# controlador.net
KiCad netlist of a schematic drawn in Altium Designer
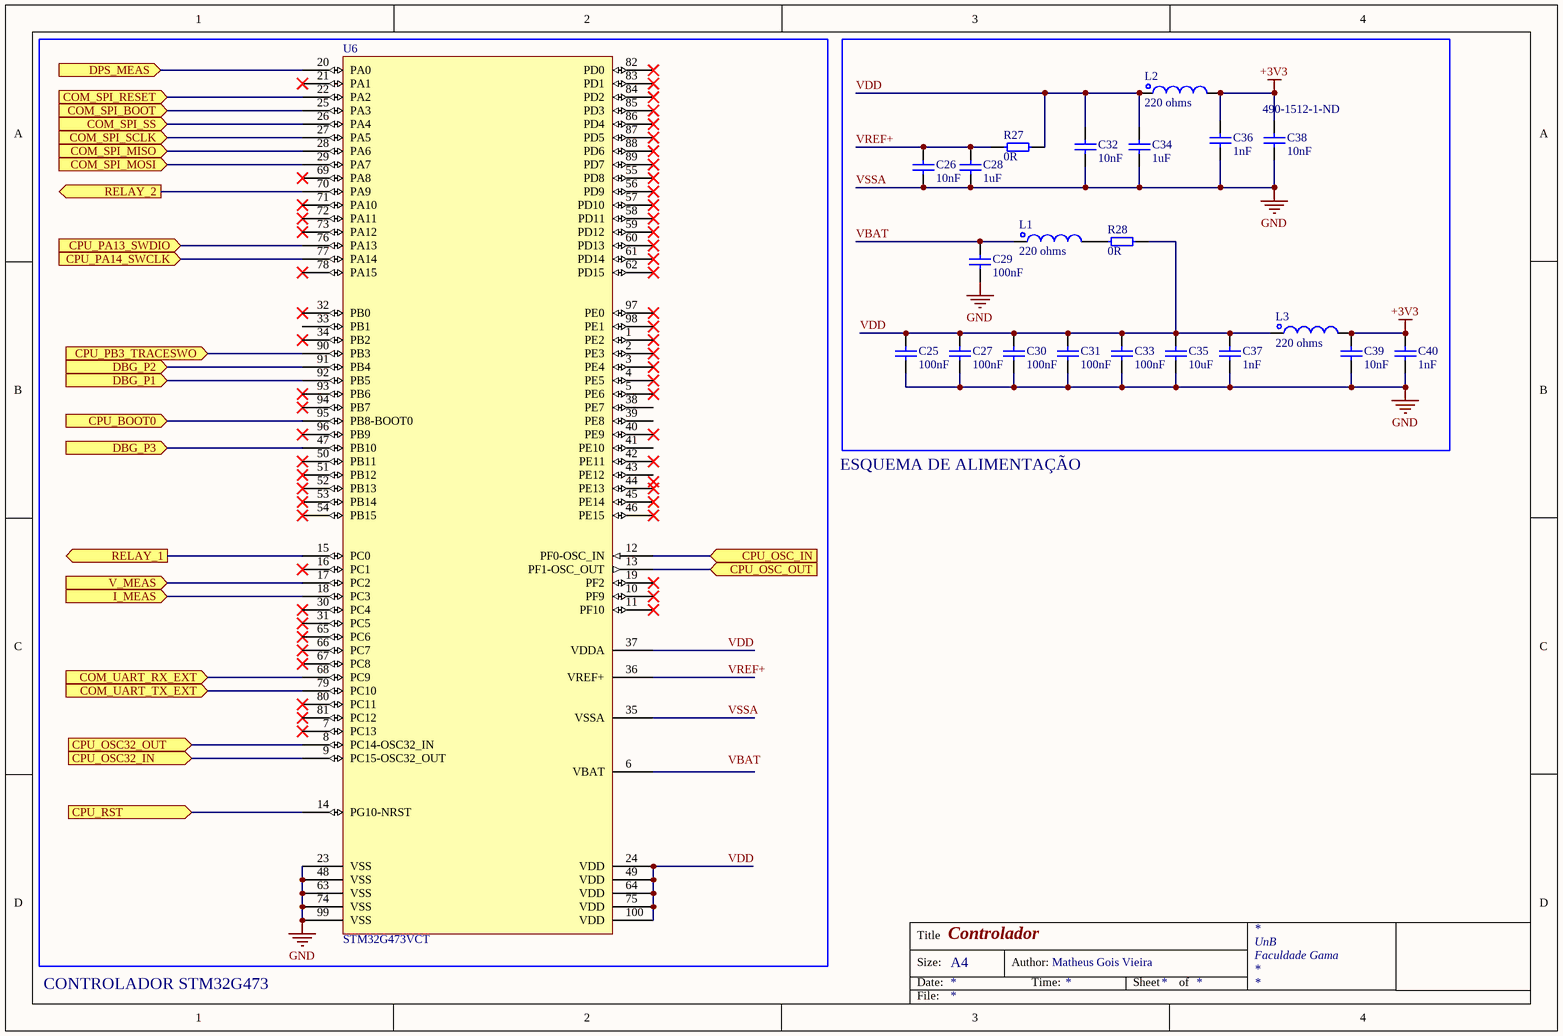
[diagram p0: controlador.SchDoc]

(export (version "E")
  (design (tool "Eeschema 10.0.6"))
  (components
    (comp (ref "C25")
      (value "100nF")
      (footprint "0603")
      (description "Capacitor Ceramic 100nF 20% 50V 0603 (1608 Metric) X7R")
      (fields (field (name "TOLERANCE") "20%") (field (name "MPN") "C0603C104M5RACTU"))
      (libsource (lib "Biblioteca_Clamper") (part "CAP CER SMD-0603 100nF - 50V"))
    )
    (comp (ref "C26")
      (value "10nF")
      (footprint "0603")
      (description "Capacitor Ceramic 10nF 10% 50V 0603 (1608 Metric) X7R")
      (fields (field (name "TOLERANCE") "10%") (field (name "MPN") "06035C103KAT4A"))
      (libsource (lib "Biblioteca_Clamper") (part "CAP CER SMD-0603 10nF - 50V"))
    )
    (comp (ref "C27")
      (value "100nF")
      (footprint "0603")
      (description "Capacitor Ceramic 100nF 20% 50V 0603 (1608 Metric) X7R")
      (fields (field (name "TOLERANCE") "20%") (field (name "MPN") "C0603C104M5RACTU"))
      (libsource (lib "Biblioteca_Clamper") (part "CAP CER SMD-0603 100nF - 50V"))
    )
    (comp (ref "C28")
      (value "1uF")
      (footprint "0603")
      (description "Capacitor Ceramic 1uF 10% 16V 0603 (1608 Metric) X7R")
      (fields (field (name "TOLERANCE") "10%") (field (name "MPN") "0603YC105KAT2A"))
      (libsource (lib "Biblioteca_Clamper") (part "CAP CER SMD-0603 1uF - 16V"))
    )
    (comp (ref "C29")
      (value "100nF")
      (footprint "0603")
      (description "Capacitor Ceramic 100nF 20% 50V 0603 (1608 Metric) X7R")
      (fields (field (name "TOLERANCE") "20%") (field (name "MPN") "C0603C104M5RACTU"))
      (libsource (lib "Biblioteca_Clamper") (part "CAP CER SMD-0603 100nF - 50V"))
    )
    (comp (ref "C30")
      (value "100nF")
      (footprint "0603")
      (description "Capacitor Ceramic 100nF 20% 50V 0603 (1608 Metric) X7R")
      (fields (field (name "TOLERANCE") "20%") (field (name "MPN") "C0603C104M5RACTU"))
      (libsource (lib "Biblioteca_Clamper") (part "CAP CER SMD-0603 100nF - 50V"))
    )
    (comp (ref "C31")
      (value "100nF")
      (footprint "0603")
      (description "Capacitor Ceramic 100nF 20% 50V 0603 (1608 Metric) X7R")
      (fields (field (name "TOLERANCE") "20%") (field (name "MPN") "C0603C104M5RACTU"))
      (libsource (lib "Biblioteca_Clamper") (part "CAP CER SMD-0603 100nF - 50V"))
    )
    (comp (ref "C32")
      (value "10nF")
      (footprint "0603")
      (description "Capacitor Ceramic 10nF 10% 50V 0603 (1608 Metric) X7R")
      (fields (field (name "TOLERANCE") "10%") (field (name "MPN") "06035C103KAT4A"))
      (libsource (lib "Biblioteca_Clamper") (part "CAP CER SMD-0603 10nF - 50V"))
    )
    (comp (ref "C33")
      (value "100nF")
      (footprint "0603")
      (description "Capacitor Ceramic 100nF 20% 50V 0603 (1608 Metric) X7R")
      (fields (field (name "TOLERANCE") "20%") (field (name "MPN") "C0603C104M5RACTU"))
      (libsource (lib "Biblioteca_Clamper") (part "CAP CER SMD-0603 100nF - 50V"))
    )
    (comp (ref "C34")
      (value "1uF")
      (footprint "0603")
      (description "Capacitor Ceramic 1uF 10% 16V 0603 (1608 Metric) X7R")
      (fields (field (name "TOLERANCE") "10%") (field (name "MPN") "0603YC105KAT2A"))
      (libsource (lib "Biblioteca_Clamper") (part "CAP CER SMD-0603 1uF - 16V"))
    )
    (comp (ref "C35")
      (value "10uF")
      (footprint "0603")
      (description "Capacitor Ceramic 10µF 10% 10V 0603 (1608 Metric) X7R")
      (fields (field (name "VOLTAGE") "10V") (field (name "TOLERANCE") "10%"))
      (libsource (lib "Biblioteca_Clamper") (part "CAP CER SMD-0603 10uF - 10V"))
    )
    (comp (ref "C36")
      (value "1nF")
      (footprint "0603")
      (description "Capacitor Ceramic 1nF 5% 50V 0603 (1608 Metric) C0G (NP0)")
      (fields (field (name "TOLERANCE") "5%") (field (name "MPN") "GRM1885C1H102JA01D"))
      (libsource (lib "Biblioteca_Clamper") (part "CAP CER SMD-0603 1nF - 50V"))
    )
    (comp (ref "C37")
      (value "1nF")
      (footprint "0603")
      (description "Capacitor Ceramic 1nF 5% 50V 0603 (1608 Metric) C0G (NP0)")
      (fields (field (name "TOLERANCE") "5%") (field (name "MPN") "GRM1885C1H102JA01D"))
      (libsource (lib "Biblioteca_Clamper") (part "CAP CER SMD-0603 1nF - 50V"))
    )
    (comp (ref "C38")
      (value "10nF")
      (footprint "0603")
      (description "Capacitor Ceramic 10nF 10% 50V 0603 (1608 Metric) X7R")
      (fields
        (field (name "TOLERANCE") "10%")
        (field (name "MPN") "06035C103KAT4A")
        (field (name "SUPPLIER PART NUMBER 1") "490-1512-1-ND")
      )
      (libsource (lib "Biblioteca_Clamper") (part "CAP CER SMD-0603 10nF - 50V"))
    )
    (comp (ref "C39")
      (value "10nF")
      (footprint "0603")
      (description "Capacitor Ceramic 10nF 10% 50V 0603 (1608 Metric) X7R")
      (fields (field (name "TOLERANCE") "10%") (field (name "MPN") "06035C103KAT4A"))
      (libsource (lib "Biblioteca_Clamper") (part "CAP CER SMD-0603 10nF - 50V"))
    )
    (comp (ref "C40")
      (value "1nF")
      (footprint "0603")
      (description "Capacitor Ceramic 1nF 5% 50V 0603 (1608 Metric) C0G (NP0)")
      (fields (field (name "TOLERANCE") "5%") (field (name "MPN") "GRM1885C1H102JA01D"))
      (libsource (lib "Biblioteca_Clamper") (part "CAP CER SMD-0603 1nF - 50V"))
    )
    (comp (ref "L1")
      (value "220 ohms")
      (footprint "0603")
      (description "INDUTOR BEAD - 2.2A - 220 OHMS 100 MHZ")
      (fields (field (name "TOLERANCE") "25%") (field (name "MPN") "BLM18KG221SZ1D"))
      (libsource (lib "Biblioteca_Clamper") (part "INDUTOR BEAD - 2.2A - 50 OHMS 100 MHZ"))
    )
    (comp (ref "L2")
      (value "220 ohms")
      (footprint "0603")
      (description "INDUTOR BEAD - 2.2A - 220 OHMS 100 MHZ")
      (fields (field (name "TOLERANCE") "25%") (field (name "MPN") "BLM18KG221SZ1D"))
      (libsource (lib "Biblioteca_Clamper") (part "INDUTOR BEAD - 2.2A - 50 OHMS 100 MHZ"))
    )
    (comp (ref "L3")
      (value "220 ohms")
      (footprint "0603")
      (description "INDUTOR BEAD - 2.2A - 220 OHMS 100 MHZ")
      (fields (field (name "TOLERANCE") "25%") (field (name "MPN") "BLM18KG221SZ1D"))
      (libsource (lib "Biblioteca_Clamper") (part "INDUTOR BEAD - 2.2A - 50 OHMS 100 MHZ"))
    )
    (comp (ref "R27")
      (value "0R")
      (footprint "0603")
      (description "Resistor Thick Film 0R Jumper 0.1W, 1/10W 0603 (1608 metric) Jumper")
      (fields (field (name "TOLERANCE") "Jumper") (field (name "MPN") "CRCW06030000Z0EA"))
      (libsource (lib "Biblioteca_Clamper") (part "RES SMD-0603 0R 1% 1/10W"))
    )
    (comp (ref "R28")
      (value "0R")
      (footprint "0603")
      (description "Resistor Thick Film 0R Jumper 0.1W, 1/10W 0603 (1608 metric) Jumper")
      (fields (field (name "TOLERANCE") "Jumper") (field (name "MPN") "CRCW06030000Z0EA"))
      (libsource (lib "") (part "RES SMD-0603 0R 1% 1/10W_1"))
    )
    (comp (ref "U6")
      (value "STM32G473VCT")
      (footprint "LQFP100_14MMX14MM")
      (fields (field (name "MANUFACTURER") "ST - Microlectronics"))
      (libsource (lib "Biblioteca_Clamper") (part "STM32G473VCT"))
    )
  )
  (nets
    (net (code "1") (name "+3V3") (class "Default")
      (node (ref "C36") (pin "2") (pinfunction "2_2") (pintype "passive"))
      (node (ref "C38") (pin "2") (pinfunction "2_2") (pintype "passive"))
      (node (ref "C39") (pin "2") (pinfunction "2_2") (pintype "passive"))
      (node (ref "C40") (pin "2") (pinfunction "2_2") (pintype "passive"))
      (node (ref "L2") (pin "2") (pinfunction "2_2") (pintype "passive"))
      (node (ref "L3") (pin "2") (pinfunction "2_2") (pintype "passive"))
    )
    (net (code "2") (name "/COM_SPI_BOOT") (class "Default")
      (node (ref "U6") (pin "25") (pinfunction "PA3_25") (pintype "bidirectional"))
    )
    (net (code "3") (name "/COM_SPI_MISO") (class "Default")
      (node (ref "U6") (pin "28") (pinfunction "PA6_28") (pintype "bidirectional"))
    )
    (net (code "4") (name "/COM_SPI_MOSI") (class "Default")
      (node (ref "U6") (pin "29") (pinfunction "PA7_29") (pintype "bidirectional"))
    )
    (net (code "5") (name "/COM_SPI_RESET") (class "Default")
      (node (ref "U6") (pin "22") (pinfunction "PA2_22") (pintype "bidirectional"))
    )
    (net (code "6") (name "/COM_SPI_SCLK") (class "Default")
      (node (ref "U6") (pin "27") (pinfunction "PA5_27") (pintype "bidirectional"))
    )
    (net (code "7") (name "/COM_SPI_SS") (class "Default")
      (node (ref "U6") (pin "26") (pinfunction "PA4_26") (pintype "bidirectional"))
    )
    (net (code "8") (name "/COM_UART_RX_EXT") (class "Default")
      (node (ref "U6") (pin "68") (pinfunction "PC9_68") (pintype "bidirectional"))
    )
    (net (code "9") (name "/COM_UART_TX_EXT") (class "Default")
      (node (ref "U6") (pin "79") (pinfunction "PC10_79") (pintype "bidirectional"))
    )
    (net (code "10") (name "/CPU_BOOT0") (class "Default")
      (node (ref "U6") (pin "95") (pinfunction "PB8-BOOT0_95") (pintype "bidirectional"))
    )
    (net (code "11") (name "/CPU_OSC32_IN") (class "Default")
      (node (ref "U6") (pin "9") (pinfunction "PC15-OSC32_OUT_9") (pintype "bidirectional"))
    )
    (net (code "12") (name "/CPU_OSC32_OUT") (class "Default")
      (node (ref "U6") (pin "8") (pinfunction "PC14-OSC32_IN_8") (pintype "bidirectional"))
    )
    (net (code "13") (name "/CPU_OSC_IN") (class "Default")
      (node (ref "U6") (pin "12") (pinfunction "PF0-OSC_IN_12") (pintype "input"))
    )
    (net (code "14") (name "/CPU_OSC_OUT") (class "Default")
      (node (ref "U6") (pin "13") (pinfunction "PF1-OSC_OUT_13") (pintype "output"))
    )
    (net (code "15") (name "/CPU_PA13_SWDIO") (class "Default")
      (node (ref "U6") (pin "76") (pinfunction "PA13_76") (pintype "bidirectional"))
    )
    (net (code "16") (name "/CPU_PA14_SWCLK") (class "Default")
      (node (ref "U6") (pin "77") (pinfunction "PA14_77") (pintype "bidirectional"))
    )
    (net (code "17") (name "/CPU_PB3_TRACESWO") (class "Default")
      (node (ref "U6") (pin "90") (pinfunction "PB3_90") (pintype "bidirectional"))
    )
    (net (code "18") (name "/CPU_RST") (class "Default")
      (node (ref "U6") (pin "14") (pinfunction "PG10-NRST_14") (pintype "bidirectional"))
    )
    (net (code "19") (name "/DBG_P1") (class "Default")
      (node (ref "U6") (pin "92") (pinfunction "PB5_92") (pintype "bidirectional"))
    )
    (net (code "20") (name "/DBG_P2") (class "Default")
      (node (ref "U6") (pin "91") (pinfunction "PB4_91") (pintype "bidirectional"))
    )
    (net (code "21") (name "/DBG_P3") (class "Default")
      (node (ref "U6") (pin "47") (pinfunction "PB10_47") (pintype "bidirectional"))
    )
    (net (code "22") (name "/DPS_MEAS") (class "Default")
      (node (ref "U6") (pin "20") (pinfunction "PA0_20") (pintype "bidirectional"))
    )
    (net (code "23") (name "/I_MEAS") (class "Default")
      (node (ref "U6") (pin "18") (pinfunction "PC3_18") (pintype "bidirectional"))
    )
    (net (code "24") (name "/RELAY_1") (class "Default")
      (node (ref "U6") (pin "15") (pinfunction "PC0_15") (pintype "bidirectional"))
    )
    (net (code "25") (name "/RELAY_2") (class "Default")
      (node (ref "U6") (pin "70") (pinfunction "PA9_70") (pintype "bidirectional"))
    )
    (net (code "26") (name "/VBAT") (class "Default")
      (node (ref "C29") (pin "1") (pinfunction "1_1") (pintype "passive"))
      (node (ref "L1") (pin "1") (pinfunction "1_1") (pintype "passive"))
    )
    (net (code "27") (name "/VDD") (class "Default")
      (node (ref "C25") (pin "1") (pinfunction "1_1") (pintype "passive"))
      (node (ref "C27") (pin "1") (pinfunction "1_1") (pintype "passive"))
      (node (ref "C30") (pin "1") (pinfunction "1_1") (pintype "passive"))
      (node (ref "C31") (pin "1") (pinfunction "1_1") (pintype "passive"))
      (node (ref "C32") (pin "2") (pinfunction "2_2") (pintype "passive"))
      (node (ref "C33") (pin "1") (pinfunction "1_1") (pintype "passive"))
      (node (ref "C34") (pin "2") (pinfunction "2_2") (pintype "passive"))
      (node (ref "C35") (pin "2") (pinfunction "2_2") (pintype "passive"))
      (node (ref "C37") (pin "2") (pinfunction "2_2") (pintype "passive"))
      (node (ref "L2") (pin "1") (pinfunction "1_1") (pintype "passive"))
      (node (ref "L3") (pin "1") (pinfunction "1_1") (pintype "passive"))
      (node (ref "R27") (pin "1") (pinfunction "1_1") (pintype "passive"))
      (node (ref "R28") (pin "2") (pinfunction "2_2") (pintype "passive"))
      (node (ref "U6") (pin "100") (pinfunction "VDD_100") (pintype "power_in"))
      (node (ref "U6") (pin "24") (pinfunction "VDD_24") (pintype "power_in"))
      (node (ref "U6") (pin "37") (pinfunction "VDDA_37") (pintype "power_in"))
      (node (ref "U6") (pin "49") (pinfunction "VDD_49") (pintype "power_in"))
      (node (ref "U6") (pin "64") (pinfunction "VDD_64") (pintype "power_in"))
      (node (ref "U6") (pin "75") (pinfunction "VDD_75") (pintype "power_in"))
    )
    (net (code "28") (name "/VREF+") (class "Default")
      (node (ref "C26") (pin "2") (pinfunction "2_2") (pintype "passive"))
      (node (ref "C28") (pin "2") (pinfunction "2_2") (pintype "passive"))
      (node (ref "R27") (pin "2") (pinfunction "2_2") (pintype "passive"))
      (node (ref "U6") (pin "36") (pinfunction "VREF+_36") (pintype "power_in"))
    )
    (net (code "29") (name "/V_MEAS") (class "Default")
      (node (ref "U6") (pin "17") (pinfunction "PC2_17") (pintype "bidirectional"))
    )
    (net (code "30") (name "GND") (class "Default")
      (node (ref "C25") (pin "2") (pinfunction "2_2") (pintype "passive"))
      (node (ref "C26") (pin "1") (pinfunction "1_1") (pintype "passive"))
      (node (ref "C27") (pin "2") (pinfunction "2_2") (pintype "passive"))
      (node (ref "C28") (pin "1") (pinfunction "1_1") (pintype "passive"))
      (node (ref "C29") (pin "2") (pinfunction "2_2") (pintype "passive"))
      (node (ref "C30") (pin "2") (pinfunction "2_2") (pintype "passive"))
      (node (ref "C31") (pin "2") (pinfunction "2_2") (pintype "passive"))
      (node (ref "C32") (pin "1") (pinfunction "1_1") (pintype "passive"))
      (node (ref "C33") (pin "2") (pinfunction "2_2") (pintype "passive"))
      (node (ref "C34") (pin "1") (pinfunction "1_1") (pintype "passive"))
      (node (ref "C35") (pin "1") (pinfunction "1_1") (pintype "passive"))
      (node (ref "C36") (pin "1") (pinfunction "1_1") (pintype "passive"))
      (node (ref "C37") (pin "1") (pinfunction "1_1") (pintype "passive"))
      (node (ref "C38") (pin "1") (pinfunction "1_1") (pintype "passive"))
      (node (ref "C39") (pin "1") (pinfunction "1_1") (pintype "passive"))
      (node (ref "C40") (pin "1") (pinfunction "1_1") (pintype "passive"))
      (node (ref "U6") (pin "23") (pinfunction "VSS_23") (pintype "power_in"))
      (node (ref "U6") (pin "35") (pinfunction "VSSA_35") (pintype "power_in"))
      (node (ref "U6") (pin "48") (pinfunction "VSS_48") (pintype "power_in"))
      (node (ref "U6") (pin "63") (pinfunction "VSS_63") (pintype "power_in"))
      (node (ref "U6") (pin "74") (pinfunction "VSS_74") (pintype "power_in"))
      (node (ref "U6") (pin "99") (pinfunction "VSS_99") (pintype "power_in"))
    )
    (net (code "31") (name "Net-(L1-Pad2)") (class "Default")
      (node (ref "L1") (pin "2") (pinfunction "2_2") (pintype "passive"))
      (node (ref "R28") (pin "1") (pinfunction "1_1") (pintype "passive"))
    )
    (net (code "32") (name "unconnected-(U6-PA1-Pad21)") (class "Default")
      (node (ref "U6") (pin "21") (pinfunction "PA1_21") (pintype "bidirectional+no_connect"))
    )
    (net (code "33") (name "unconnected-(U6-PA8-Pad69)") (class "Default")
      (node (ref "U6") (pin "69") (pinfunction "PA8_69") (pintype "bidirectional+no_connect"))
    )
    (net (code "34") (name "unconnected-(U6-PA10-Pad71)") (class "Default")
      (node (ref "U6") (pin "71") (pinfunction "PA10_71") (pintype "bidirectional+no_connect"))
    )
    (net (code "35") (name "unconnected-(U6-PA11-Pad72)") (class "Default")
      (node (ref "U6") (pin "72") (pinfunction "PA11_72") (pintype "bidirectional+no_connect"))
    )
    (net (code "36") (name "unconnected-(U6-PA12-Pad73)") (class "Default")
      (node (ref "U6") (pin "73") (pinfunction "PA12_73") (pintype "bidirectional+no_connect"))
    )
    (net (code "37") (name "unconnected-(U6-PA15-Pad78)") (class "Default")
      (node (ref "U6") (pin "78") (pinfunction "PA15_78") (pintype "bidirectional+no_connect"))
    )
    (net (code "38") (name "unconnected-(U6-PB0-Pad32)") (class "Default")
      (node (ref "U6") (pin "32") (pinfunction "PB0_32") (pintype "bidirectional+no_connect"))
    )
    (net (code "39") (name "unconnected-(U6-PB1-Pad33)") (class "Default")
      (node (ref "U6") (pin "33") (pinfunction "PB1_33") (pintype "bidirectional"))
    )
    (net (code "40") (name "unconnected-(U6-PB2-Pad34)") (class "Default")
      (node (ref "U6") (pin "34") (pinfunction "PB2_34") (pintype "bidirectional+no_connect"))
    )
    (net (code "41") (name "unconnected-(U6-PB6-Pad93)") (class "Default")
      (node (ref "U6") (pin "93") (pinfunction "PB6_93") (pintype "bidirectional+no_connect"))
    )
    (net (code "42") (name "unconnected-(U6-PB7-Pad94)") (class "Default")
      (node (ref "U6") (pin "94") (pinfunction "PB7_94") (pintype "bidirectional+no_connect"))
    )
    (net (code "43") (name "unconnected-(U6-PB9-Pad96)") (class "Default")
      (node (ref "U6") (pin "96") (pinfunction "PB9_96") (pintype "bidirectional+no_connect"))
    )
    (net (code "44") (name "unconnected-(U6-PB11-Pad50)") (class "Default")
      (node (ref "U6") (pin "50") (pinfunction "PB11_50") (pintype "bidirectional+no_connect"))
    )
    (net (code "45") (name "unconnected-(U6-PB12-Pad51)") (class "Default")
      (node (ref "U6") (pin "51") (pinfunction "PB12_51") (pintype "bidirectional+no_connect"))
    )
    (net (code "46") (name "unconnected-(U6-PB13-Pad52)") (class "Default")
      (node (ref "U6") (pin "52") (pinfunction "PB13_52") (pintype "bidirectional+no_connect"))
    )
    (net (code "47") (name "unconnected-(U6-PB14-Pad53)") (class "Default")
      (node (ref "U6") (pin "53") (pinfunction "PB14_53") (pintype "bidirectional+no_connect"))
    )
    (net (code "48") (name "unconnected-(U6-PB15-Pad54)") (class "Default")
      (node (ref "U6") (pin "54") (pinfunction "PB15_54") (pintype "bidirectional+no_connect"))
    )
    (net (code "49") (name "unconnected-(U6-PC1-Pad16)") (class "Default")
      (node (ref "U6") (pin "16") (pinfunction "PC1_16") (pintype "bidirectional+no_connect"))
    )
    (net (code "50") (name "unconnected-(U6-PC4-Pad30)") (class "Default")
      (node (ref "U6") (pin "30") (pinfunction "PC4_30") (pintype "bidirectional+no_connect"))
    )
    (net (code "51") (name "unconnected-(U6-PC5-Pad31)") (class "Default")
      (node (ref "U6") (pin "31") (pinfunction "PC5_31") (pintype "bidirectional+no_connect"))
    )
    (net (code "52") (name "unconnected-(U6-PC6-Pad65)") (class "Default")
      (node (ref "U6") (pin "65") (pinfunction "PC6_65") (pintype "bidirectional+no_connect"))
    )
    (net (code "53") (name "unconnected-(U6-PC7-Pad66)") (class "Default")
      (node (ref "U6") (pin "66") (pinfunction "PC7_66") (pintype "bidirectional+no_connect"))
    )
    (net (code "54") (name "unconnected-(U6-PC8-Pad67)") (class "Default")
      (node (ref "U6") (pin "67") (pinfunction "PC8_67") (pintype "bidirectional+no_connect"))
    )
    (net (code "55") (name "unconnected-(U6-PC11-Pad80)") (class "Default")
      (node (ref "U6") (pin "80") (pinfunction "PC11_80") (pintype "bidirectional+no_connect"))
    )
    (net (code "56") (name "unconnected-(U6-PC12-Pad81)") (class "Default")
      (node (ref "U6") (pin "81") (pinfunction "PC12_81") (pintype "bidirectional+no_connect"))
    )
    (net (code "57") (name "unconnected-(U6-PC13-Pad7)") (class "Default")
      (node (ref "U6") (pin "7") (pinfunction "PC13_7") (pintype "bidirectional+no_connect"))
    )
    (net (code "58") (name "unconnected-(U6-PD0-Pad82)") (class "Default")
      (node (ref "U6") (pin "82") (pinfunction "PD0_82") (pintype "bidirectional+no_connect"))
    )
    (net (code "59") (name "unconnected-(U6-PD1-Pad83)") (class "Default")
      (node (ref "U6") (pin "83") (pinfunction "PD1_83") (pintype "bidirectional+no_connect"))
    )
    (net (code "60") (name "unconnected-(U6-PD2-Pad84)") (class "Default")
      (node (ref "U6") (pin "84") (pinfunction "PD2_84") (pintype "bidirectional+no_connect"))
    )
    (net (code "61") (name "unconnected-(U6-PD3-Pad85)") (class "Default")
      (node (ref "U6") (pin "85") (pinfunction "PD3_85") (pintype "bidirectional+no_connect"))
    )
    (net (code "62") (name "unconnected-(U6-PD4-Pad86)") (class "Default")
      (node (ref "U6") (pin "86") (pinfunction "PD4_86") (pintype "bidirectional+no_connect"))
    )
    (net (code "63") (name "unconnected-(U6-PD5-Pad87)") (class "Default")
      (node (ref "U6") (pin "87") (pinfunction "PD5_87") (pintype "bidirectional+no_connect"))
    )
    (net (code "64") (name "unconnected-(U6-PD6-Pad88)") (class "Default")
      (node (ref "U6") (pin "88") (pinfunction "PD6_88") (pintype "bidirectional+no_connect"))
    )
    (net (code "65") (name "unconnected-(U6-PD7-Pad89)") (class "Default")
      (node (ref "U6") (pin "89") (pinfunction "PD7_89") (pintype "bidirectional+no_connect"))
    )
    (net (code "66") (name "unconnected-(U6-PD8-Pad55)") (class "Default")
      (node (ref "U6") (pin "55") (pinfunction "PD8_55") (pintype "bidirectional+no_connect"))
    )
    (net (code "67") (name "unconnected-(U6-PD9-Pad56)") (class "Default")
      (node (ref "U6") (pin "56") (pinfunction "PD9_56") (pintype "bidirectional+no_connect"))
    )
    (net (code "68") (name "unconnected-(U6-PD10-Pad57)") (class "Default")
      (node (ref "U6") (pin "57") (pinfunction "PD10_57") (pintype "bidirectional+no_connect"))
    )
    (net (code "69") (name "unconnected-(U6-PD11-Pad58)") (class "Default")
      (node (ref "U6") (pin "58") (pinfunction "PD11_58") (pintype "bidirectional+no_connect"))
    )
    (net (code "70") (name "unconnected-(U6-PD12-Pad59)") (class "Default")
      (node (ref "U6") (pin "59") (pinfunction "PD12_59") (pintype "bidirectional+no_connect"))
    )
    (net (code "71") (name "unconnected-(U6-PD13-Pad60)") (class "Default")
      (node (ref "U6") (pin "60") (pinfunction "PD13_60") (pintype "bidirectional+no_connect"))
    )
    (net (code "72") (name "unconnected-(U6-PD14-Pad61)") (class "Default")
      (node (ref "U6") (pin "61") (pinfunction "PD14_61") (pintype "bidirectional+no_connect"))
    )
    (net (code "73") (name "unconnected-(U6-PD15-Pad62)") (class "Default")
      (node (ref "U6") (pin "62") (pinfunction "PD15_62") (pintype "bidirectional+no_connect"))
    )
    (net (code "74") (name "unconnected-(U6-PE0-Pad97)") (class "Default")
      (node (ref "U6") (pin "97") (pinfunction "PE0_97") (pintype "bidirectional+no_connect"))
    )
    (net (code "75") (name "unconnected-(U6-PE1-Pad98)") (class "Default")
      (node (ref "U6") (pin "98") (pinfunction "PE1_98") (pintype "bidirectional+no_connect"))
    )
    (net (code "76") (name "unconnected-(U6-PE2-Pad1)") (class "Default")
      (node (ref "U6") (pin "1") (pinfunction "PE2_1") (pintype "bidirectional+no_connect"))
    )
    (net (code "77") (name "unconnected-(U6-PE3-Pad2)") (class "Default")
      (node (ref "U6") (pin "2") (pinfunction "PE3_2") (pintype "bidirectional+no_connect"))
    )
    (net (code "78") (name "unconnected-(U6-PE4-Pad3)") (class "Default")
      (node (ref "U6") (pin "3") (pinfunction "PE4_3") (pintype "bidirectional+no_connect"))
    )
    (net (code "79") (name "unconnected-(U6-PE5-Pad4)") (class "Default")
      (node (ref "U6") (pin "4") (pinfunction "PE5_4") (pintype "bidirectional+no_connect"))
    )
    (net (code "80") (name "unconnected-(U6-PE6-Pad5)") (class "Default")
      (node (ref "U6") (pin "5") (pinfunction "PE6_5") (pintype "bidirectional+no_connect"))
    )
    (net (code "81") (name "unconnected-(U6-PE7-Pad38)") (class "Default")
      (node (ref "U6") (pin "38") (pinfunction "PE7_38") (pintype "bidirectional"))
    )
    (net (code "82") (name "unconnected-(U6-PE8-Pad39)") (class "Default")
      (node (ref "U6") (pin "39") (pinfunction "PE8_39") (pintype "bidirectional"))
    )
    (net (code "83") (name "unconnected-(U6-PE9-Pad40)") (class "Default")
      (node (ref "U6") (pin "40") (pinfunction "PE9_40") (pintype "bidirectional+no_connect"))
    )
    (net (code "84") (name "unconnected-(U6-PE10-Pad41)") (class "Default")
      (node (ref "U6") (pin "41") (pinfunction "PE10_41") (pintype "bidirectional"))
    )
    (net (code "85") (name "unconnected-(U6-PE11-Pad42)") (class "Default")
      (node (ref "U6") (pin "42") (pinfunction "PE11_42") (pintype "bidirectional+no_connect"))
    )
    (net (code "86") (name "unconnected-(U6-PE12-Pad43)") (class "Default")
      (node (ref "U6") (pin "43") (pinfunction "PE12_43") (pintype "bidirectional"))
    )
    (net (code "87") (name "unconnected-(U6-PE13-Pad44)") (class "Default")
      (node (ref "U6") (pin "44") (pinfunction "PE13_44") (pintype "bidirectional+no_connect"))
    )
    (net (code "88") (name "unconnected-(U6-PE14-Pad45)") (class "Default")
      (node (ref "U6") (pin "45") (pinfunction "PE14_45") (pintype "bidirectional+no_connect"))
    )
    (net (code "89") (name "unconnected-(U6-PE15-Pad46)") (class "Default")
      (node (ref "U6") (pin "46") (pinfunction "PE15_46") (pintype "bidirectional+no_connect"))
    )
    (net (code "90") (name "unconnected-(U6-PF2-Pad19)") (class "Default")
      (node (ref "U6") (pin "19") (pinfunction "PF2_19") (pintype "bidirectional+no_connect"))
    )
    (net (code "91") (name "unconnected-(U6-PF9-Pad10)") (class "Default")
      (node (ref "U6") (pin "10") (pinfunction "PF9_10") (pintype "bidirectional+no_connect"))
    )
    (net (code "92") (name "unconnected-(U6-PF10-Pad11)") (class "Default")
      (node (ref "U6") (pin "11") (pinfunction "PF10_11") (pintype "bidirectional+no_connect"))
    )
    (net (code "93") (name "unconnected-(U6-VBAT-Pad6)") (class "Default")
      (node (ref "U6") (pin "6") (pinfunction "VBAT_6") (pintype "power_in"))
    )
  )
)
